# MCU.net
KiCad netlist of a schematic drawn in Altium Designer
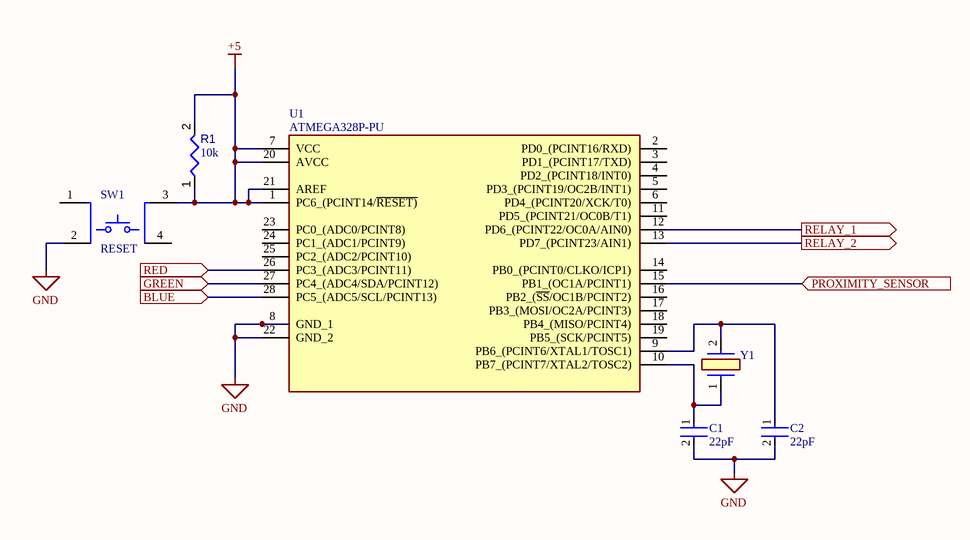
[diagram p0: MCU.SchDoc]

(export (version "E")
  (design (tool "Eeschema 10.0.6"))
  (components
    (comp (ref "C1")
      (value "22pF")
      (footprint "FP-RCE0DB-MFG")
      (description "Cap Ceramic 22pF 100V C0G ±5% Radial 2.5mm +125°C Ammo Pack")
      (fields (field (name "VOLTAGE") "100V") (field (name "TOLERANCE") "5%"))
      (libsource (lib "Altium Content Vault") (part "b4654b650e69147ec39a6b967a45e02"))
    )
    (comp (ref "C2")
      (value "22pF")
      (footprint "FP-RCE0DB-MFG")
      (description "Cap Ceramic 22pF 100V C0G ±5% Radial 2.5mm +125°C Ammo Pack")
      (fields (field (name "VOLTAGE") "100V") (field (name "TOLERANCE") "5%"))
      (libsource (lib "Altium Content Vault") (part "b4654b650e69147ec39a6b967a45e02"))
    )
    (comp (ref "R1")
      (value "10k")
      (footprint "RESA60-630X240")
      (description "Axial Resistor, 10 KOhm, +/- 1%, 0.25 W, -55 to 155 degC, 2-Pin THD, RoHS, Bulk")
      (fields (field (name "TOLERANCE") "1%") (field (name "POWER") "250mW"))
      (libsource (lib "Nidula  Gunawardana") (part "RES-2"))
    )
    (comp (ref "SW1")
      (value "RESET")
      (footprint "FP-SKQBARA010-MFG")
      (description "SKQBARA010 Switch Tactile N.O. SPST Round Button PC Pins 0.05A 12VDC 1.57N Thru-Hole Automotive")
      (libsource (lib "Altium Content Vault") (part "e22b01984cfc11d83da275cd8cd0ddf"))
    )
    (comp (ref "U1")
      (value "ATMEGA328P-PU")
      (footprint "SamacSys:DIP794W53P254L3467H457Q28N")
      (description "Integrated Circuit")
      (fields (field (name "MOUSER PART NUMBER") "556-ATMEGA328P-PU"))
      (libsource (lib "*") (part "ATMEGA328P-PU"))
    )
    (comp (ref "Y1")
      (value "ECS-160-S-4X")
      (footprint "SamacSys:ECS160S4X")
      (description "Crystal or Oscillator")
      (fields (field (name "MOUSER PART NUMBER") "520-HCU1600-SX"))
      (libsource (lib "*") (part "ECS-160-S-4X"))
    )
  )
  (nets
    (net (code "1") (name "+5") (class "Default")
      (node (ref "R1") (pin "1") (pinfunction "1_1") (pintype "passive"))
      (node (ref "R1") (pin "2") (pinfunction "2_2") (pintype "passive"))
      (node (ref "SW1") (pin "3") (pinfunction "3_3") (pintype "passive"))
      (node (ref "U1") (pin "1") (pinfunction "PC6_(PCINT14/~{RESET)}_1") (pintype "passive"))
      (node (ref "U1") (pin "20") (pinfunction "AVCC_20") (pintype "passive"))
      (node (ref "U1") (pin "21") (pinfunction "AREF_21") (pintype "passive"))
      (node (ref "U1") (pin "7") (pinfunction "VCC_7") (pintype "passive"))
    )
    (net (code "2") (name "/BLUE") (class "Default")
      (node (ref "U1") (pin "28") (pinfunction "PC5_(ADC5/SCL/PCINT13)_28") (pintype "passive"))
    )
    (net (code "3") (name "/GREEN") (class "Default")
      (node (ref "U1") (pin "27") (pinfunction "PC4_(ADC4/SDA/PCINT12)_27") (pintype "passive"))
    )
    (net (code "4") (name "/PROXIMITY_SENSOR") (class "Default")
      (node (ref "U1") (pin "15") (pinfunction "PB1_(OC1A/PCINT1)_15") (pintype "passive"))
    )
    (net (code "5") (name "/RED") (class "Default")
      (node (ref "U1") (pin "26") (pinfunction "PC3_(ADC3/PCINT11)_26") (pintype "passive"))
    )
    (net (code "6") (name "/RELAY_1") (class "Default")
      (node (ref "U1") (pin "12") (pinfunction "PD6_(PCINT22/OC0A/AIN0)_12") (pintype "passive"))
    )
    (net (code "7") (name "/RELAY_2") (class "Default")
      (node (ref "U1") (pin "13") (pinfunction "PD7_(PCINT23/AIN1)_13") (pintype "passive"))
    )
    (net (code "8") (name "GND") (class "Default")
      (node (ref "C1") (pin "2") (pinfunction "2_2") (pintype "passive"))
      (node (ref "C2") (pin "2") (pinfunction "2_2") (pintype "passive"))
      (node (ref "SW1") (pin "2") (pinfunction "2_2") (pintype "passive"))
      (node (ref "U1") (pin "22") (pinfunction "GND_2_22") (pintype "passive"))
      (node (ref "U1") (pin "8") (pinfunction "GND_1_8") (pintype "passive"))
    )
    (net (code "9") (name "Net-(U1-PB6_(PCINT6{slash}XTAL1{slash}TOSC1))") (class "Default")
      (node (ref "C2") (pin "1") (pinfunction "1_1") (pintype "passive"))
      (node (ref "U1") (pin "9") (pinfunction "PB6_(PCINT6/XTAL1/TOSC1)_9") (pintype "passive"))
      (node (ref "Y1") (pin "2") (pinfunction "2_2") (pintype "passive"))
    )
    (net (code "10") (name "Net-(U1-PB7_(PCINT7{slash}XTAL2{slash}TOSC2))") (class "Default")
      (node (ref "C1") (pin "1") (pinfunction "1_1") (pintype "passive"))
      (node (ref "U1") (pin "10") (pinfunction "PB7_(PCINT7/XTAL2/TOSC2)_10") (pintype "passive"))
      (node (ref "Y1") (pin "1") (pinfunction "1_1") (pintype "passive"))
    )
    (net (code "11") (name "unconnected-(SW1-Pad1)") (class "Default")
      (node (ref "SW1") (pin "1") (pinfunction "1_1") (pintype "passive"))
    )
    (net (code "12") (name "unconnected-(SW1-Pad4)") (class "Default")
      (node (ref "SW1") (pin "4") (pinfunction "4_4") (pintype "passive"))
    )
    (net (code "13") (name "unconnected-(U1-PB0_(PCINT0{slash}CLKO{slash}ICP1)-Pad14)") (class "Default")
      (node (ref "U1") (pin "14") (pinfunction "PB0_(PCINT0/CLKO/ICP1)_14") (pintype "passive"))
    )
    (net (code "14") (name "unconnected-(U1-PB2_(~{SS}{slash}OC1B{slash}PCINT2)-Pad16)") (class "Default")
      (node (ref "U1") (pin "16") (pinfunction "PB2_(~{SS}/OC1B/PCINT2)_16") (pintype "passive"))
    )
    (net (code "15") (name "unconnected-(U1-PB3_(MOSI{slash}OC2A{slash}PCINT3)-Pad17)") (class "Default")
      (node (ref "U1") (pin "17") (pinfunction "PB3_(MOSI/OC2A/PCINT3)_17") (pintype "passive"))
    )
    (net (code "16") (name "unconnected-(U1-PB4_(MISO{slash}PCINT4)-Pad18)") (class "Default")
      (node (ref "U1") (pin "18") (pinfunction "PB4_(MISO/PCINT4)_18") (pintype "passive"))
    )
    (net (code "17") (name "unconnected-(U1-PB5_(SCK{slash}PCINT5)-Pad19)") (class "Default")
      (node (ref "U1") (pin "19") (pinfunction "PB5_(SCK/PCINT5)_19") (pintype "passive"))
    )
    (net (code "18") (name "unconnected-(U1-PC0_(ADC0{slash}PCINT8)-Pad23)") (class "Default")
      (node (ref "U1") (pin "23") (pinfunction "PC0_(ADC0/PCINT8)_23") (pintype "passive"))
    )
    (net (code "19") (name "unconnected-(U1-PC1_(ADC1{slash}PCINT9)-Pad24)") (class "Default")
      (node (ref "U1") (pin "24") (pinfunction "PC1_(ADC1/PCINT9)_24") (pintype "passive"))
    )
    (net (code "20") (name "unconnected-(U1-PC2_(ADC2{slash}PCINT10)-Pad25)") (class "Default")
      (node (ref "U1") (pin "25") (pinfunction "PC2_(ADC2/PCINT10)_25") (pintype "passive"))
    )
    (net (code "21") (name "unconnected-(U1-PD0_(PCINT16{slash}RXD)-Pad2)") (class "Default")
      (node (ref "U1") (pin "2") (pinfunction "PD0_(PCINT16/RXD)_2") (pintype "passive"))
    )
    (net (code "22") (name "unconnected-(U1-PD1_(PCINT17{slash}TXD)-Pad3)") (class "Default")
      (node (ref "U1") (pin "3") (pinfunction "PD1_(PCINT17/TXD)_3") (pintype "passive"))
    )
    (net (code "23") (name "unconnected-(U1-PD2_(PCINT18{slash}INT0)-Pad4)") (class "Default")
      (node (ref "U1") (pin "4") (pinfunction "PD2_(PCINT18/INT0)_4") (pintype "passive"))
    )
    (net (code "24") (name "unconnected-(U1-PD3_(PCINT19{slash}OC2B{slash}INT1)-Pad5)") (class "Default")
      (node (ref "U1") (pin "5") (pinfunction "PD3_(PCINT19/OC2B/INT1)_5") (pintype "passive"))
    )
    (net (code "25") (name "unconnected-(U1-PD4_(PCINT20{slash}XCK{slash}T0)-Pad6)") (class "Default")
      (node (ref "U1") (pin "6") (pinfunction "PD4_(PCINT20/XCK/T0)_6") (pintype "passive"))
    )
    (net (code "26") (name "unconnected-(U1-PD5_(PCINT21{slash}OC0B{slash}T1)-Pad11)") (class "Default")
      (node (ref "U1") (pin "11") (pinfunction "PD5_(PCINT21/OC0B/T1)_11") (pintype "passive"))
    )
  )
)
